# IsolatedPWM.net
KiCad netlist of a schematic drawn in Altium Designer
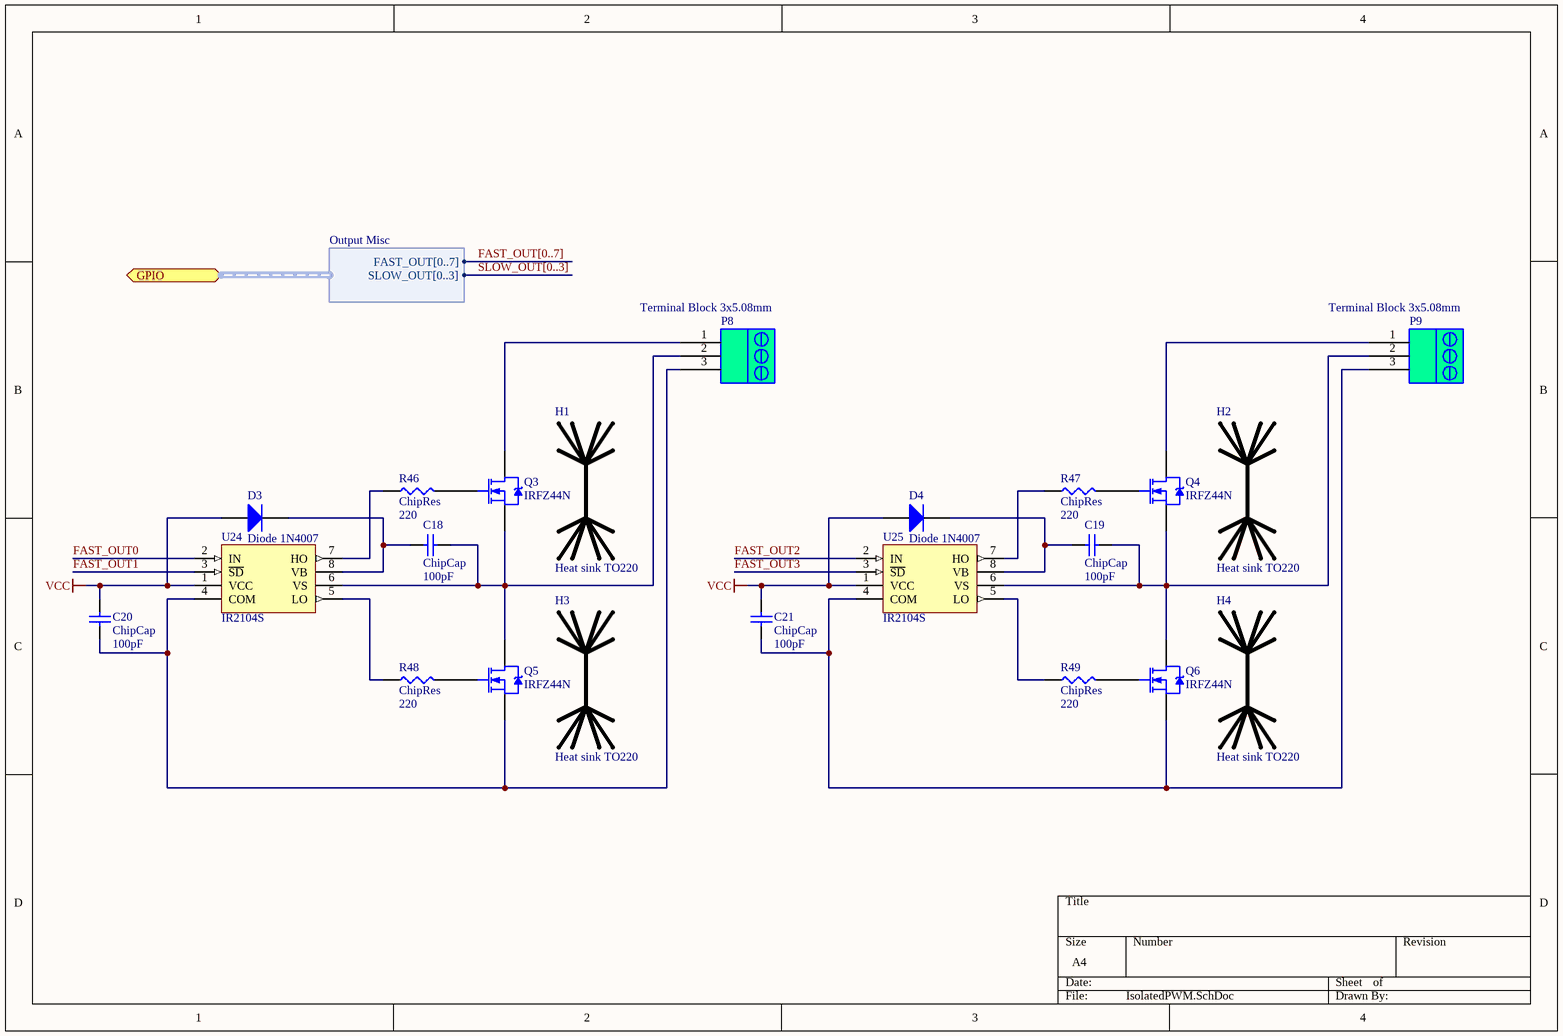
[diagram p0: IsolatedPWM.SchDoc]

(export (version "E")
  (design (tool "Eeschema 10.0.6"))
  (components
    (comp (ref "C18")
      (value "ChipCap")
      (footprint "CAP1206")
      (description "Capacitor")
      (fields (field (name "ALTIUM_VALUE") "100pF") (field (name "PUBLISHER") "Altium Limited"))
      (libsource (lib "Common Devices") (part "ChipCap"))
    )
    (comp (ref "C19")
      (value "ChipCap")
      (footprint "CAP1206")
      (description "Capacitor")
      (fields (field (name "ALTIUM_VALUE") "100pF") (field (name "PUBLISHER") "Altium Limited"))
      (libsource (lib "Common Devices") (part "ChipCap"))
    )
    (comp (ref "C20")
      (value "ChipCap")
      (footprint "CAP0805")
      (description "Capacitor")
      (fields (field (name "ALTIUM_VALUE") "100pF") (field (name "PUBLISHER") "Altium Limited"))
      (libsource (lib "Common Devices") (part "ChipCap"))
    )
    (comp (ref "C21")
      (value "ChipCap")
      (footprint "CAP0805")
      (description "Capacitor")
      (fields (field (name "ALTIUM_VALUE") "100pF") (field (name "PUBLISHER") "Altium Limited"))
      (libsource (lib "Common Devices") (part "ChipCap"))
    )
    (comp (ref "D3")
      (value "Diode 1N4007")
      (footprint "DO-41")
      (description "1 Amp General Purpose Rectifier")
      (fields (field (name "PUBLISHER") "Altium Limited"))
      (libsource (lib "Miscellaneous Devices") (part "Diode 1N4007"))
    )
    (comp (ref "D4")
      (value "Diode 1N4007")
      (footprint "DO-41")
      (description "1 Amp General Purpose Rectifier")
      (fields (field (name "PUBLISHER") "Altium Limited"))
      (libsource (lib "Miscellaneous Devices") (part "Diode 1N4007"))
    )
    (comp (ref "H1")
      (value "Heat sink TO220")
      (footprint "HeatSink_TO220")
      (description "Heat Sink TO220")
      (libsource (lib "Heat Sinks") (part "HeatSink_TO220"))
    )
    (comp (ref "H2")
      (value "Heat sink TO220")
      (footprint "HeatSink_TO220")
      (description "Heat Sink TO220")
      (libsource (lib "Heat Sinks") (part "HeatSink_TO220"))
    )
    (comp (ref "H3")
      (value "Heat sink TO220")
      (footprint "HeatSink_TO220")
      (description "Heat Sink TO220")
      (libsource (lib "Heat Sinks") (part "HeatSink_TO220"))
    )
    (comp (ref "H4")
      (value "Heat sink TO220")
      (footprint "HeatSink_TO220")
      (description "Heat Sink TO220")
      (libsource (lib "Heat Sinks") (part "HeatSink_TO220"))
    )
    (comp (ref "P8")
      (value "Terminal Block 3x5.08mm")
      (footprint "Socket 3x5.08")
      (description "Terminal Block Socket Right Angle 3x5.08mm 2-Wall")
      (libsource (lib "IndustrialConnectors") (part "Socket_3x5.08_RA_2Wall"))
    )
    (comp (ref "P9")
      (value "Terminal Block 3x5.08mm")
      (footprint "Socket 3x5.08")
      (description "Terminal Block Socket Right Angle 3x5.08mm 2-Wall")
      (libsource (lib "IndustrialConnectors") (part "Socket_3x5.08_RA_2Wall"))
    )
    (comp (ref "Q3")
      (value "IRFZ44N")
      (footprint "TO-220AB")
      (description "HEXFET Power MOSFET")
      (fields (field (name "PUBLISHER") "Altium Limited"))
      (libsource (lib "IR Discrete MOSFET - Power") (part "IRFZ44N"))
    )
    (comp (ref "Q4")
      (value "IRFZ44N")
      (footprint "TO-220AB")
      (description "HEXFET Power MOSFET")
      (fields (field (name "PUBLISHER") "Altium Limited"))
      (libsource (lib "IR Discrete MOSFET - Power") (part "IRFZ44N"))
    )
    (comp (ref "Q5")
      (value "IRFZ44N")
      (footprint "TO-220AB")
      (description "HEXFET Power MOSFET")
      (fields (field (name "PUBLISHER") "Altium Limited"))
      (libsource (lib "IR Discrete MOSFET - Power") (part "IRFZ44N"))
    )
    (comp (ref "Q6")
      (value "IRFZ44N")
      (footprint "TO-220AB")
      (description "HEXFET Power MOSFET")
      (fields (field (name "PUBLISHER") "Altium Limited"))
      (libsource (lib "IR Discrete MOSFET - Power") (part "IRFZ44N"))
    )
    (comp (ref "R46")
      (value "ChipRes")
      (footprint "RES0805")
      (description "Chip resistor")
      (fields (field (name "ALTIUM_VALUE") "220"))
      (libsource (lib "Common Devices") (part "ChipRes"))
    )
    (comp (ref "R47")
      (value "ChipRes")
      (footprint "RES0805")
      (description "Chip resistor")
      (fields (field (name "ALTIUM_VALUE") "220"))
      (libsource (lib "Common Devices") (part "ChipRes"))
    )
    (comp (ref "R48")
      (value "ChipRes")
      (footprint "RES0805")
      (description "Chip resistor")
      (fields (field (name "ALTIUM_VALUE") "220"))
      (libsource (lib "Common Devices") (part "ChipRes"))
    )
    (comp (ref "R49")
      (value "ChipRes")
      (footprint "RES0805")
      (description "Chip resistor")
      (fields (field (name "ALTIUM_VALUE") "220"))
      (libsource (lib "Common Devices") (part "ChipRes"))
    )
    (comp (ref "U24")
      (value "IR2104S")
      (footprint "SO-8_N")
      (description "High and Low Side Driver")
      (fields (field (name "PUBLISHER") "Altium Limited"))
      (libsource (lib "IR Interface Bridge Driver") (part "IR2104S"))
    )
    (comp (ref "U25")
      (value "IR2104S")
      (footprint "SO-8_N")
      (description "High and Low Side Driver")
      (fields (field (name "PUBLISHER") "Altium Limited"))
      (libsource (lib "IR Interface Bridge Driver") (part "IR2104S"))
    )
  )
  (nets
    (net (code "11") (name "/FAST_OUT0") (class "Default")
      (node (ref "U24") (pin "2") (pinfunction "IN_2") (pintype "input"))
    )
    (net (code "12") (name "/FAST_OUT1") (class "Default")
      (node (ref "U24") (pin "3") (pinfunction "~{SD}_3") (pintype "input"))
    )
    (net (code "13") (name "/FAST_OUT2") (class "Default")
      (node (ref "U25") (pin "2") (pinfunction "IN_2") (pintype "input"))
    )
    (net (code "14") (name "/FAST_OUT3") (class "Default")
      (node (ref "U25") (pin "3") (pinfunction "~{SD}_3") (pintype "input"))
    )
    (net (code "18") (name "Net-(D3-K)") (class "Default")
      (node (ref "C18") (pin "2") (pinfunction "2_2") (pintype "passive"))
      (node (ref "D3") (pin "2") (pinfunction "K_2") (pintype "passive"))
      (node (ref "U24") (pin "8") (pinfunction "VB_8") (pintype "power_in"))
    )
    (net (code "19") (name "Net-(D4-K)") (class "Default")
      (node (ref "C19") (pin "2") (pinfunction "2_2") (pintype "passive"))
      (node (ref "D4") (pin "2") (pinfunction "K_2") (pintype "passive"))
      (node (ref "U25") (pin "8") (pinfunction "VB_8") (pintype "power_in"))
    )
    (net (code "20") (name "Net-(Q3-D)") (class "Default")
      (node (ref "P8") (pin "1") (pintype "passive"))
      (node (ref "Q3") (pin "2") (pinfunction "D_2") (pintype "passive"))
    )
    (net (code "21") (name "Net-(Q3-G)") (class "Default")
      (node (ref "Q3") (pin "1") (pinfunction "G_1") (pintype "passive"))
      (node (ref "R46") (pin "2") (pintype "passive"))
    )
    (net (code "22") (name "Net-(Q3-S)") (class "Default")
      (node (ref "C18") (pin "1") (pinfunction "1_1") (pintype "passive"))
      (node (ref "P8") (pin "2") (pintype "passive"))
      (node (ref "Q3") (pin "3") (pinfunction "S_3") (pintype "passive"))
      (node (ref "Q5") (pin "2") (pinfunction "D_2") (pintype "passive"))
      (node (ref "U24") (pin "6") (pinfunction "VS_6") (pintype "power_in"))
    )
    (net (code "23") (name "Net-(Q4-D)") (class "Default")
      (node (ref "P9") (pin "1") (pintype "passive"))
      (node (ref "Q4") (pin "2") (pinfunction "D_2") (pintype "passive"))
    )
    (net (code "24") (name "Net-(Q4-G)") (class "Default")
      (node (ref "Q4") (pin "1") (pinfunction "G_1") (pintype "passive"))
      (node (ref "R47") (pin "2") (pintype "passive"))
    )
    (net (code "25") (name "Net-(Q4-S)") (class "Default")
      (node (ref "C19") (pin "1") (pinfunction "1_1") (pintype "passive"))
      (node (ref "P9") (pin "2") (pintype "passive"))
      (node (ref "Q4") (pin "3") (pinfunction "S_3") (pintype "passive"))
      (node (ref "Q6") (pin "2") (pinfunction "D_2") (pintype "passive"))
      (node (ref "U25") (pin "6") (pinfunction "VS_6") (pintype "power_in"))
    )
    (net (code "26") (name "Net-(Q5-G)") (class "Default")
      (node (ref "Q5") (pin "1") (pinfunction "G_1") (pintype "passive"))
      (node (ref "R48") (pin "2") (pintype "passive"))
    )
    (net (code "27") (name "Net-(Q5-S)") (class "Default")
      (node (ref "C20") (pin "1") (pinfunction "1_1") (pintype "passive"))
      (node (ref "P8") (pin "3") (pintype "passive"))
      (node (ref "Q5") (pin "3") (pinfunction "S_3") (pintype "passive"))
      (node (ref "U24") (pin "4") (pinfunction "COM_4") (pintype "power_in"))
    )
    (net (code "28") (name "Net-(Q6-G)") (class "Default")
      (node (ref "Q6") (pin "1") (pinfunction "G_1") (pintype "passive"))
      (node (ref "R49") (pin "2") (pintype "passive"))
    )
    (net (code "29") (name "Net-(Q6-S)") (class "Default")
      (node (ref "C21") (pin "1") (pinfunction "1_1") (pintype "passive"))
      (node (ref "P9") (pin "3") (pintype "passive"))
      (node (ref "Q6") (pin "3") (pinfunction "S_3") (pintype "passive"))
      (node (ref "U25") (pin "4") (pinfunction "COM_4") (pintype "power_in"))
    )
    (net (code "30") (name "Net-(U24-HO)") (class "Default")
      (node (ref "R46") (pin "1") (pintype "passive"))
      (node (ref "U24") (pin "7") (pinfunction "HO_7") (pintype "output"))
    )
    (net (code "31") (name "Net-(U24-LO)") (class "Default")
      (node (ref "R48") (pin "1") (pintype "passive"))
      (node (ref "U24") (pin "5") (pinfunction "LO_5") (pintype "output"))
    )
    (net (code "32") (name "Net-(U25-HO)") (class "Default")
      (node (ref "R47") (pin "1") (pintype "passive"))
      (node (ref "U25") (pin "7") (pinfunction "HO_7") (pintype "output"))
    )
    (net (code "33") (name "Net-(U25-LO)") (class "Default")
      (node (ref "R49") (pin "1") (pintype "passive"))
      (node (ref "U25") (pin "5") (pinfunction "LO_5") (pintype "output"))
    )
    (net (code "34") (name "VCC") (class "Default")
      (node (ref "C20") (pin "2") (pinfunction "2_2") (pintype "passive"))
      (node (ref "C21") (pin "2") (pinfunction "2_2") (pintype "passive"))
      (node (ref "D3") (pin "1") (pinfunction "A_1") (pintype "passive"))
      (node (ref "D4") (pin "1") (pinfunction "A_1") (pintype "passive"))
      (node (ref "U24") (pin "1") (pinfunction "VCC_1") (pintype "power_in"))
      (node (ref "U25") (pin "1") (pinfunction "VCC_1") (pintype "power_in"))
    )
  )
)
